# Connectors_USB.net
KiCad netlist of a schematic drawn in Altium Designer
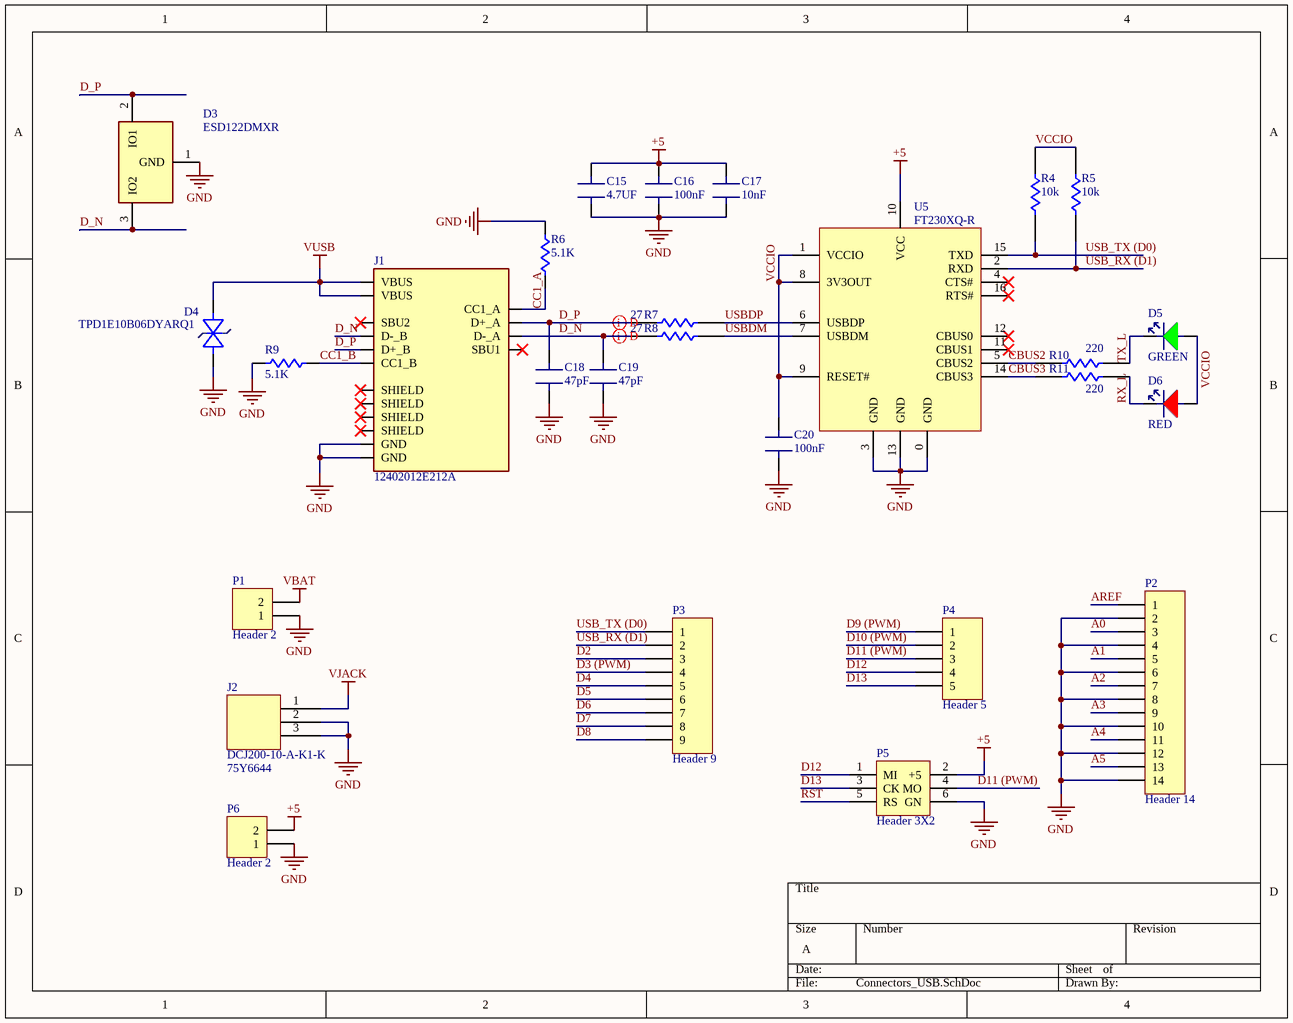
[diagram p0: Connectors_USB.SchDoc]

(export (version "E")
  (design (tool "Eeschema 10.0.6"))
  (components
    (comp (ref "C15")
      (value "4.7UF")
      (footprint "CAPC1608X90N")
      (description "CAP CER 4.7UF 25V X5R 0603")
      (libsource (lib "MESchLib") (part "1276-1903-6-ND"))
    )
    (comp (ref "C16")
      (value "100nF")
      (footprint "CAPC1608X90N")
      (description "CAP CER 0.1UF 50V 10% X7R 0603")
      (libsource (lib "MESchLib") (part "C14663"))
    )
    (comp (ref "C17")
      (value "10nF")
      (footprint "CAPC1608X90N")
      (description "CAP CER 10000PF 50V X7R 0603")
      (libsource (lib "MESchLib") (part "1292-1386-6-ND"))
    )
    (comp (ref "C18")
      (value "47pF")
      (footprint "CAPC1608X90N")
      (description "CAP CER 47PF 50V C0G/NPO 0603")
      (libsource (lib "MESchLib") (part "311-3899-6-ND"))
    )
    (comp (ref "C19")
      (value "47pF")
      (footprint "CAPC1608X90N")
      (description "CAP CER 47PF 50V C0G/NPO 0603")
      (libsource (lib "MESchLib") (part "311-3899-6-ND"))
    )
    (comp (ref "C20")
      (value "100nF")
      (footprint "CAPC1608X90N")
      (description "CAP CER 0.1UF 50V 10% X7R 0603")
      (libsource (lib "MESchLib") (part "C14663"))
    )
    (comp (ref "D3")
      (value "ESD122DMXR")
      (footprint "3-X2SON (1x0.6)")
      (description "TVS DIODE 3.6VWM 8.4VC 3X2SON")
      (libsource (lib "MESchLib") (part "ESD122DMXR"))
    )
    (comp (ref "D4")
      (value "TPD1E10B06DYARQ1")
      (footprint "SOD-523")
      (description "14V (Typ) Clamp 6A (8/20µs) Ipp Tvs Diode Surface Mount SOT-5X3")
      (libsource (lib "MESchLib") (part "TPD1E10B06DYARQ1"))
    )
    (comp (ref "D5")
      (value "GREEN")
      (footprint "LED: 0805G")
      (description "LED GREEN CLEAR 0805 SMD")
      (libsource (lib "MESchLib") (part "732-4983-6-ND"))
    )
    (comp (ref "D6")
      (value "RED")
      (footprint "LED: 0805R")
      (description "LED RED CLEAR 0805 SMD")
      (libsource (lib "MESchLib") (part "732-4985-6-ND"))
    )
    (comp (ref "J1")
      (value "12402012E212A")
      (footprint "AMPHENOL_12402012E212A")
      (description "CONN RCP USB2.0 TYP C 24P SMD RA")
      (libsource (lib "MESchLib") (part "12402012E212A"))
    )
    (comp (ref "J2")
      (value "DCJ200-10-A-K1-K")
      (footprint "DC JACK")
      (description "Power Barrel Connector Jack 2.05mm ID (0.081\"), 5.50mm OD (0.217\") Through Hole, Right Angle")
      (fields (field (name "SUPPLIER PART NUMBER 1") "75Y6644"))
      (libsource (lib "MESchLib") (part "2073-DCJ200-10-A-K1-K-ND"))
    )
    (comp (ref "P1")
      (value "Header 2")
      (footprint "HDR1X2")
      (description "Header, 2-Pin")
      (fields (field (name "PUBLISHER") "Altium Limited"))
      (libsource (lib "Miscellaneous Connectors") (part "Header 2"))
    )
    (comp (ref "P2")
      (value "Header 14")
      (footprint "HDR1X14")
      (description "Header, 14-Pin")
      (fields (field (name "PUBLISHER") "Altium Limited"))
      (libsource (lib "Miscellaneous Connectors") (part "Header 14"))
    )
    (comp (ref "P3")
      (value "Header 9")
      (footprint "HDR1X9")
      (description "Header, 9-Pin")
      (fields (field (name "PUBLISHER") "Altium Limited"))
      (libsource (lib "Miscellaneous Connectors") (part "Header 9"))
    )
    (comp (ref "P4")
      (value "Header 5")
      (footprint "HDR1X5")
      (description "Header, 5-Pin")
      (fields (field (name "PUBLISHER") "Altium Limited"))
      (libsource (lib "Miscellaneous Connectors") (part "Header 5"))
    )
    (comp (ref "P5")
      (value "Header 3X2")
      (footprint "HDR2X3")
      (description "Header, 3-Pin, Dual row")
      (fields (field (name "PUBLISHER") "Altium Limited"))
      (libsource (lib "Miscellaneous Connectors") (part "Header 3X2"))
    )
    (comp (ref "P6")
      (value "Header 2")
      (footprint "HDR1X2")
      (description "Header, 2-Pin")
      (fields (field (name "PUBLISHER") "Altium Limited"))
      (libsource (lib "Miscellaneous Connectors") (part "Header 2"))
    )
    (comp (ref "R4")
      (value "10k")
      (footprint "RESC1608X55N")
      (description "RES SMD 10K OHM 1% 1/10W 0603")
      (libsource (lib "MESchLib") (part "RC0603FR-0710KL"))
    )
    (comp (ref "R5")
      (value "10k")
      (footprint "RESC1608X55N")
      (description "RES SMD 10K OHM 1% 1/10W 0603")
      (libsource (lib "MESchLib") (part "RC0603FR-0710KL"))
    )
    (comp (ref "R6")
      (value "5.1K")
      (footprint "RESC1608X55N")
      (description "RES 5.1K OHM 1% 1/10W 0603")
      (libsource (lib "MESchLib") (part "541-CRCW06035K10FKEBCDKR-ND"))
    )
    (comp (ref "R7")
      (value "27")
      (footprint "RESC1608X55N")
      (description "RES SMD 27 OHM 1% 1/10W 0603")
      (libsource (lib "MESchLib") (part "CR0603-FX-27R0ELFDKR-ND"))
    )
    (comp (ref "R8")
      (value "27")
      (footprint "RESC1608X55N")
      (description "RES SMD 27 OHM 1% 1/10W 0603")
      (libsource (lib "MESchLib") (part "CR0603-FX-27R0ELFDKR-ND"))
    )
    (comp (ref "R9")
      (value "5.1K")
      (footprint "RESC1608X55N")
      (description "RES 5.1K OHM 1% 1/10W 0603")
      (libsource (lib "MESchLib") (part "541-CRCW06035K10FKEBCDKR-ND"))
    )
    (comp (ref "R10")
      (value "220")
      (footprint "RESC1608X55N")
      (description "RES SMD 220 OHM 1% 1/10W 0603")
      (libsource (lib "MESchLib") (part "311-220HRDKR-ND"))
    )
    (comp (ref "R11")
      (value "220")
      (footprint "RESC1608X55N")
      (description "RES SMD 220 OHM 1% 1/10W 0603")
      (libsource (lib "MESchLib") (part "311-220HRDKR-ND"))
    )
    (comp (ref "U5")
      (value "FT230XQ-R")
      (footprint "16-QFN (4x4)")
      (description "USB Bridge, USB to UART USB 2.0 UART Interface 16-QFN (4x4)")
      (libsource (lib "MESchLib") (part "FT230XQ-R"))
    )
  )
  (nets
    (net (code "1") (name "+5") (class "Default")
      (node (ref "C15") (pin "2") (pinfunction "B_2") (pintype "passive"))
      (node (ref "C16") (pin "2") (pinfunction "B_2") (pintype "passive"))
      (node (ref "C17") (pin "2") (pinfunction "B_2") (pintype "passive"))
      (node (ref "P5") (pin "2") (pinfunction "+5_2") (pintype "passive"))
      (node (ref "P6") (pin "2") (pinfunction "2_2") (pintype "passive"))
      (node (ref "U5") (pin "10") (pinfunction "VCC_10") (pintype "passive"))
    )
    (net (code "2") (name "/A0") (class "Default")
      (node (ref "P2") (pin "3") (pinfunction "3_3") (pintype "passive"))
    )
    (net (code "3") (name "/A1") (class "Default")
      (node (ref "P2") (pin "5") (pinfunction "5_5") (pintype "passive"))
    )
    (net (code "4") (name "/A2") (class "Default")
      (node (ref "P2") (pin "7") (pinfunction "7_7") (pintype "passive"))
    )
    (net (code "5") (name "/A3") (class "Default")
      (node (ref "P2") (pin "9") (pinfunction "9_9") (pintype "passive"))
    )
    (net (code "6") (name "/A4") (class "Default")
      (node (ref "P2") (pin "11") (pinfunction "11_11") (pintype "passive"))
    )
    (net (code "7") (name "/A5") (class "Default")
      (node (ref "P2") (pin "13") (pinfunction "13_13") (pintype "passive"))
    )
    (net (code "8") (name "/AREF") (class "Default")
      (node (ref "P2") (pin "1") (pinfunction "1_1") (pintype "passive"))
    )
    (net (code "9") (name "/CBUS2") (class "Default")
      (node (ref "R10") (pin "1") (pinfunction "1_1") (pintype "passive"))
      (node (ref "U5") (pin "5") (pinfunction "CBUS2_5") (pintype "passive"))
    )
    (net (code "10") (name "/CBUS3") (class "Default")
      (node (ref "R11") (pin "1") (pinfunction "1_1") (pintype "passive"))
      (node (ref "U5") (pin "14") (pinfunction "CBUS3_14") (pintype "passive"))
    )
    (net (code "11") (name "/CC1_A") (class "Default")
      (node (ref "J1") (pin "A5") (pinfunction "CC1_A_A5") (pintype "passive"))
      (node (ref "R6") (pin "1") (pinfunction "1_1") (pintype "passive"))
    )
    (net (code "12") (name "/CC1_B") (class "Default")
      (node (ref "J1") (pin "B5") (pinfunction "CC1_B_B5") (pintype "passive"))
      (node (ref "R9") (pin "1") (pinfunction "1_1") (pintype "passive"))
    )
    (net (code "13") (name "/D2") (class "Default")
      (node (ref "P3") (pin "3") (pinfunction "3_3") (pintype "passive"))
    )
    (net (code "14") (name "/D3 (PWM)") (class "Default")
      (node (ref "P3") (pin "4") (pinfunction "4_4") (pintype "passive"))
    )
    (net (code "15") (name "/D4") (class "Default")
      (node (ref "P3") (pin "5") (pinfunction "5_5") (pintype "passive"))
    )
    (net (code "16") (name "/D5") (class "Default")
      (node (ref "P3") (pin "6") (pinfunction "6_6") (pintype "passive"))
    )
    (net (code "17") (name "/D6") (class "Default")
      (node (ref "P3") (pin "7") (pinfunction "7_7") (pintype "passive"))
    )
    (net (code "18") (name "/D7") (class "Default")
      (node (ref "P3") (pin "8") (pinfunction "8_8") (pintype "passive"))
    )
    (net (code "19") (name "/D8") (class "Default")
      (node (ref "P3") (pin "9") (pinfunction "9_9") (pintype "passive"))
    )
    (net (code "20") (name "/D9 (PWM)") (class "Default")
      (node (ref "P4") (pin "1") (pinfunction "1_1") (pintype "passive"))
    )
    (net (code "21") (name "/D10 (PWM)") (class "Default")
      (node (ref "P4") (pin "2") (pinfunction "2_2") (pintype "passive"))
    )
    (net (code "22") (name "/D11 (PWM)") (class "Default")
      (node (ref "P4") (pin "3") (pinfunction "3_3") (pintype "passive"))
      (node (ref "P5") (pin "4") (pinfunction "MO_4") (pintype "passive"))
    )
    (net (code "23") (name "/D12") (class "Default")
      (node (ref "P4") (pin "4") (pinfunction "4_4") (pintype "passive"))
      (node (ref "P5") (pin "1") (pinfunction "MI_1") (pintype "passive"))
    )
    (net (code "24") (name "/D13") (class "Default")
      (node (ref "P4") (pin "5") (pinfunction "5_5") (pintype "passive"))
      (node (ref "P5") (pin "3") (pinfunction "CK_3") (pintype "passive"))
    )
    (net (code "25") (name "/D_N") (class "Default")
      (node (ref "C19") (pin "2") (pinfunction "B_2") (pintype "passive"))
      (node (ref "D3") (pin "3") (pinfunction "IO2_3") (pintype "passive"))
      (node (ref "J1") (pin "A7") (pinfunction "D-_A_A7") (pintype "passive"))
      (node (ref "J1") (pin "B7") (pinfunction "D-_B_B7") (pintype "passive"))
      (node (ref "R8") (pin "1") (pinfunction "1_1") (pintype "passive"))
    )
    (net (code "26") (name "/D_P") (class "Default")
      (node (ref "C18") (pin "2") (pinfunction "B_2") (pintype "passive"))
      (node (ref "D3") (pin "2") (pinfunction "IO1_2") (pintype "passive"))
      (node (ref "J1") (pin "A6") (pinfunction "D+_A_A6") (pintype "passive"))
      (node (ref "J1") (pin "B6") (pinfunction "D+_B_B6") (pintype "passive"))
      (node (ref "R7") (pin "1") (pinfunction "1_1") (pintype "passive"))
    )
    (net (code "27") (name "/RST") (class "Default")
      (node (ref "P5") (pin "5") (pinfunction "RS_5") (pintype "passive"))
    )
    (net (code "28") (name "/RX_L") (class "Default")
      (node (ref "D6") (pin "1") (pinfunction "C_1") (pintype "passive"))
      (node (ref "R11") (pin "2") (pinfunction "2_2") (pintype "passive"))
    )
    (net (code "29") (name "/TX_L") (class "Default")
      (node (ref "D5") (pin "1") (pinfunction "C_1") (pintype "passive"))
      (node (ref "R10") (pin "2") (pinfunction "2_2") (pintype "passive"))
    )
    (net (code "30") (name "/USBDM") (class "Default")
      (node (ref "R8") (pin "2") (pinfunction "2_2") (pintype "passive"))
      (node (ref "U5") (pin "7") (pinfunction "USBDM_7") (pintype "passive"))
    )
    (net (code "31") (name "/USBDP") (class "Default")
      (node (ref "R7") (pin "2") (pinfunction "2_2") (pintype "passive"))
      (node (ref "U5") (pin "6") (pinfunction "USBDP_6") (pintype "passive"))
    )
    (net (code "32") (name "/USB_RX (D1)") (class "Default")
      (node (ref "P3") (pin "2") (pinfunction "2_2") (pintype "passive"))
      (node (ref "R5") (pin "1") (pinfunction "1_1") (pintype "passive"))
      (node (ref "U5") (pin "2") (pinfunction "RXD_2") (pintype "passive"))
    )
    (net (code "33") (name "/USB_TX (D0)") (class "Default")
      (node (ref "P3") (pin "1") (pinfunction "1_1") (pintype "passive"))
      (node (ref "R4") (pin "1") (pinfunction "1_1") (pintype "passive"))
      (node (ref "U5") (pin "15") (pinfunction "TXD_15") (pintype "passive"))
    )
    (net (code "34") (name "/VCCIO") (class "Default")
      (node (ref "C20") (pin "2") (pinfunction "B_2") (pintype "passive"))
      (node (ref "D5") (pin "2") (pinfunction "A_2") (pintype "passive"))
      (node (ref "D6") (pin "2") (pinfunction "A_2") (pintype "passive"))
      (node (ref "R4") (pin "2") (pinfunction "2_2") (pintype "passive"))
      (node (ref "R5") (pin "2") (pinfunction "2_2") (pintype "passive"))
      (node (ref "U5") (pin "1") (pinfunction "VCCIO_1") (pintype "passive"))
      (node (ref "U5") (pin "8") (pinfunction "3V3OUT_8") (pintype "passive"))
      (node (ref "U5") (pin "9") (pinfunction "RESET#_9") (pintype "passive"))
    )
    (net (code "35") (name "GND") (class "Default")
      (node (ref "C15") (pin "1") (pinfunction "A_1") (pintype "passive"))
      (node (ref "C16") (pin "1") (pinfunction "A_1") (pintype "passive"))
      (node (ref "C17") (pin "1") (pinfunction "A_1") (pintype "passive"))
      (node (ref "C18") (pin "1") (pinfunction "A_1") (pintype "passive"))
      (node (ref "C19") (pin "1") (pinfunction "A_1") (pintype "passive"))
      (node (ref "C20") (pin "1") (pinfunction "A_1") (pintype "passive"))
      (node (ref "D3") (pin "1") (pinfunction "GND_1") (pintype "passive"))
      (node (ref "D4") (pin "2") (pinfunction "2_2") (pintype "passive"))
      (node (ref "J1") (pin "A1_B12") (pinfunction "GND_A1_B12") (pintype "passive"))
      (node (ref "J1") (pin "B1_A12") (pinfunction "GND_B1_A12") (pintype "passive"))
      (node (ref "J2") (pin "2") (pinfunction "2_2") (pintype "passive"))
      (node (ref "J2") (pin "3") (pinfunction "3_3") (pintype "passive"))
      (node (ref "P1") (pin "1") (pinfunction "1_1") (pintype "passive"))
      (node (ref "P2") (pin "10") (pinfunction "10_10") (pintype "passive"))
      (node (ref "P2") (pin "12") (pinfunction "12_12") (pintype "passive"))
      (node (ref "P2") (pin "14") (pinfunction "14_14") (pintype "passive"))
      (node (ref "P2") (pin "2") (pinfunction "2_2") (pintype "passive"))
      (node (ref "P2") (pin "4") (pinfunction "4_4") (pintype "passive"))
      (node (ref "P2") (pin "6") (pinfunction "6_6") (pintype "passive"))
      (node (ref "P2") (pin "8") (pinfunction "8_8") (pintype "passive"))
      (node (ref "P5") (pin "6") (pinfunction "GN_6") (pintype "passive"))
      (node (ref "P6") (pin "1") (pinfunction "1_1") (pintype "passive"))
      (node (ref "R6") (pin "2") (pinfunction "2_2") (pintype "passive"))
      (node (ref "R9") (pin "2") (pinfunction "2_2") (pintype "passive"))
      (node (ref "U5") (pin "0") (pinfunction "GND_0") (pintype "passive"))
      (node (ref "U5") (pin "13") (pinfunction "GND_13") (pintype "passive"))
      (node (ref "U5") (pin "3") (pinfunction "GND_3") (pintype "passive"))
    )
    (net (code "36") (name "VBAT") (class "Default")
      (node (ref "P1") (pin "2") (pinfunction "2_2") (pintype "passive"))
    )
    (net (code "37") (name "VJACK") (class "Default")
      (node (ref "J2") (pin "1") (pinfunction "1_1") (pintype "passive"))
    )
    (net (code "38") (name "VUSB") (class "Default")
      (node (ref "D4") (pin "1") (pinfunction "1_1") (pintype "passive"))
      (node (ref "J1") (pin "A4_B9") (pinfunction "VBUS_A4_B9") (pintype "passive"))
      (node (ref "J1") (pin "B4_A9") (pinfunction "VBUS_B4_A9") (pintype "passive"))
    )
    (net (code "39") (name "unconnected-(J1-SBU1-PadA8)") (class "Default")
      (node (ref "J1") (pin "A8") (pinfunction "SBU1_A8") (pintype "passive+no_connect"))
    )
    (net (code "40") (name "unconnected-(J1-SBU2-PadB8)") (class "Default")
      (node (ref "J1") (pin "B8") (pinfunction "SBU2_B8") (pintype "passive+no_connect"))
    )
    (net (code "41") (name "unconnected-(J1-SHIELD-PadSH1)") (class "Default")
      (node (ref "J1") (pin "SH1") (pinfunction "SHIELD_SH1") (pintype "passive+no_connect"))
    )
    (net (code "42") (name "unconnected-(J1-SHIELD-PadSH2)") (class "Default")
      (node (ref "J1") (pin "SH2") (pinfunction "SHIELD_SH2") (pintype "passive+no_connect"))
    )
    (net (code "43") (name "unconnected-(J1-SHIELD-PadSH3)") (class "Default")
      (node (ref "J1") (pin "SH3") (pinfunction "SHIELD_SH3") (pintype "passive+no_connect"))
    )
    (net (code "44") (name "unconnected-(J1-SHIELD-PadSH4)") (class "Default")
      (node (ref "J1") (pin "SH4") (pinfunction "SHIELD_SH4") (pintype "passive+no_connect"))
    )
    (net (code "45") (name "unconnected-(U5-CBUS0-Pad12)") (class "Default")
      (node (ref "U5") (pin "12") (pinfunction "CBUS0_12") (pintype "passive+no_connect"))
    )
    (net (code "46") (name "unconnected-(U5-CBUS1-Pad11)") (class "Default")
      (node (ref "U5") (pin "11") (pinfunction "CBUS1_11") (pintype "passive+no_connect"))
    )
    (net (code "47") (name "unconnected-(U5-CTS#-Pad4)") (class "Default")
      (node (ref "U5") (pin "4") (pinfunction "CTS#_4") (pintype "passive+no_connect"))
    )
    (net (code "48") (name "unconnected-(U5-RTS#-Pad16)") (class "Default")
      (node (ref "U5") (pin "16") (pinfunction "RTS#_16") (pintype "passive+no_connect"))
    )
  )
)
